# switches_connectors.net
KiCad netlist of a schematic drawn in Altium Designer
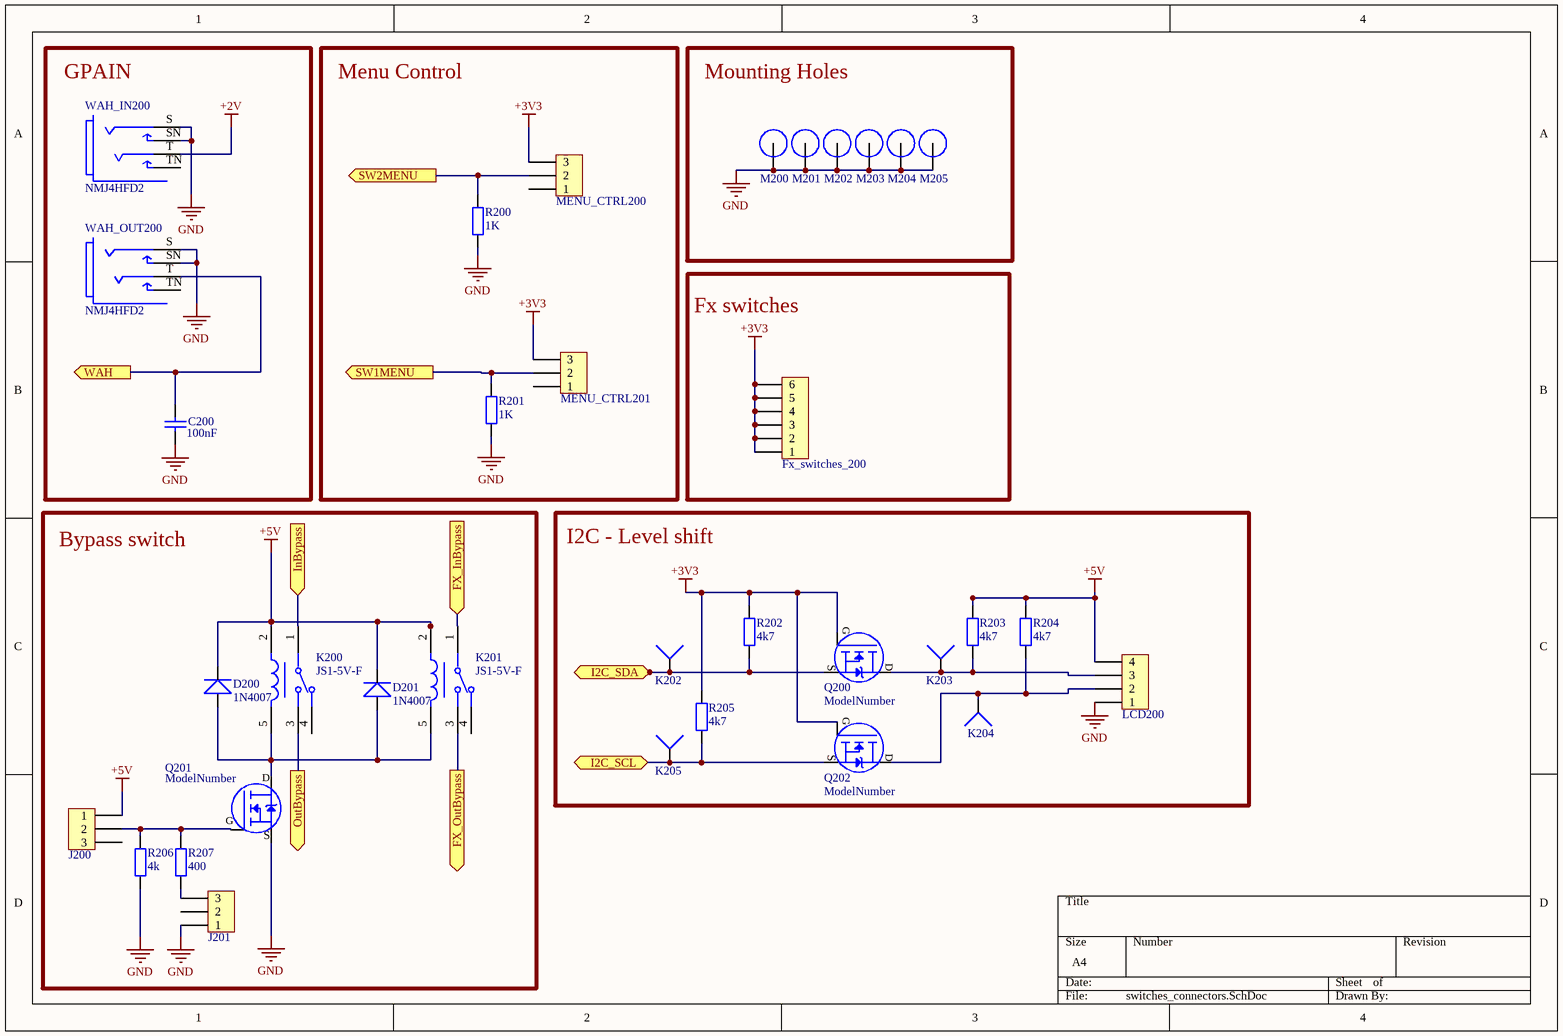
[diagram p0: switches_connectors.SchDoc]

(export (version "E")
  (design (tool "Eeschema 10.0.6"))
  (components
    (comp (ref "C200")
      (value "100nF")
      (footprint "Cap-1")
      (fields (field (name "Comment") "Cap"))
      (libsource (lib "AAURacing") (part "Capacitor 1 space"))
    )
    (comp (ref "D200")
      (value "1N4007")
      (footprint "1N4007")
      (libsource (lib "mit_seje_library") (part "1N4007"))
    )
    (comp (ref "D201")
      (value "1N4007")
      (footprint "1N4007")
      (libsource (lib "mit_seje_library") (part "1N4007"))
    )
    (comp (ref "Fx_switches_200")
      (value "Header 1x6")
      (footprint "Header 1x6")
      (libsource (lib "AAURacing") (part "Header 1x6"))
    )
    (comp (ref "J200")
      (value "Header 1x3")
      (footprint "Header 1x3")
      (libsource (lib "") (part "Header 1x3_1"))
    )
    (comp (ref "J201")
      (value "Header 1x3")
      (footprint "Header 1x3")
      (libsource (lib "AAURacing") (part "Header 1x3"))
    )
    (comp (ref "K200")
      (value "JS1-5V-F")
      (footprint "FP-JS1-5V-F-MFG")
      (description "RELAY GEN PURPOSE SPDT 10A 5V")
      (fields
        (field (name "OCTOPART") "https://octopart.com/js1-5v-f-panasonic-39428621")
        (field (name "MANUFACTURER") "Panasonic")
      )
      (libsource (lib "Altium Content Vault") (part "250623531296f86beaf95f2bc4a6d4c"))
    )
    (comp (ref "K201")
      (value "JS1-5V-F")
      (footprint "FP-JS1-5V-F-MFG")
      (description "RELAY GEN PURPOSE SPDT 10A 5V")
      (fields
        (field (name "OCTOPART") "https://octopart.com/js1-5v-f-panasonic-39428621")
        (field (name "MANUFACTURER") "Panasonic")
      )
      (libsource (lib "Altium Content Vault") (part "250623531296f86beaf95f2bc4a6d4c"))
    )
    (comp (ref "K202") (value "Wire") (footprint "Wire 1.5mm") (libsource (lib "AAURacing") (part "Wire")))
    (comp (ref "K203") (value "Wire") (footprint "Wire 1.5mm") (libsource (lib "AAURacing") (part "Wire")))
    (comp (ref "K204") (value "Wire") (footprint "Wire 1.5mm") (libsource (lib "AAURacing") (part "Wire")))
    (comp (ref "K205") (value "Wire") (footprint "Wire 1.5mm") (libsource (lib "AAURacing") (part "Wire")))
    (comp (ref "LCD200")
      (value "Header 1x4")
      (footprint "Header 1x4")
      (libsource (lib "AAURacing") (part "Header 1x4"))
    )
    (comp (ref "M200")
      (value "Screw Hole")
      (footprint "M3 Hole")
      (libsource (lib "AAURacing") (part "Screw Hole"))
    )
    (comp (ref "M201")
      (value "Screw Hole")
      (footprint "M3 Hole")
      (libsource (lib "AAURacing") (part "Screw Hole"))
    )
    (comp (ref "M202")
      (value "Screw Hole")
      (footprint "M3 Hole")
      (libsource (lib "AAURacing") (part "Screw Hole"))
    )
    (comp (ref "M203")
      (value "Screw Hole")
      (footprint "M3 Hole")
      (libsource (lib "AAURacing") (part "Screw Hole"))
    )
    (comp (ref "M204")
      (value "Screw Hole")
      (footprint "M3 Hole")
      (libsource (lib "AAURacing") (part "Screw Hole"))
    )
    (comp (ref "M205")
      (value "Screw Hole")
      (footprint "M3 Hole")
      (libsource (lib "AAURacing") (part "Screw Hole"))
    )
    (comp (ref "MENU_CTRL200")
      (value "Header 1x3")
      (footprint "Header 1x3")
      (libsource (lib "AAURacing") (part "Header 1x3"))
    )
    (comp (ref "MENU_CTRL201")
      (value "Header 1x3")
      (footprint "Header 1x3")
      (libsource (lib "AAURacing") (part "Header 1x3"))
    )
    (comp (ref "Q200")
      (value "ModelNum")
      (footprint "TO-92_straight")
      (fields (field (name "MODEL") "ModelNumber"))
      (libsource (lib "AAURacing") (part "MOSFET N-Channel"))
    )
    (comp (ref "Q201")
      (value "ModelNum")
      (footprint "TO-220")
      (fields (field (name "MODEL") "ModelNumber"))
      (libsource (lib "AAURacing") (part "MOSFET N-Channel"))
    )
    (comp (ref "Q202")
      (value "ModelNum")
      (footprint "TO-92_straight")
      (fields (field (name "MODEL") "ModelNumber"))
      (libsource (lib "AAURacing") (part "MOSFET N-Channel"))
    )
    (comp (ref "R200")
      (value "1K")
      (footprint "RES THT 9mm")
      (fields (field (name "Comment") "Resistor"))
      (libsource (lib "AAURacing") (part "Resistor"))
    )
    (comp (ref "R201")
      (value "1K")
      (footprint "RES THT 9mm")
      (fields (field (name "Comment") "Resistor"))
      (libsource (lib "AAURacing") (part "Resistor"))
    )
    (comp (ref "R202")
      (value "4k7")
      (footprint "RES THT 9mm")
      (fields (field (name "Comment") "Resistor"))
      (libsource (lib "AAURacing") (part "Resistor"))
    )
    (comp (ref "R203")
      (value "4k7")
      (footprint "RES THT 9mm")
      (fields (field (name "Comment") "Resistor"))
      (libsource (lib "AAURacing") (part "Resistor"))
    )
    (comp (ref "R204")
      (value "4k7")
      (footprint "RES THT 9mm")
      (fields (field (name "Comment") "Resistor"))
      (libsource (lib "AAURacing") (part "Resistor"))
    )
    (comp (ref "R205")
      (value "4k7")
      (footprint "RES THT 9mm")
      (fields (field (name "Comment") "Resistor"))
      (libsource (lib "AAURacing") (part "Resistor"))
    )
    (comp (ref "R206")
      (value "4k")
      (footprint "RES THT 9mm")
      (fields (field (name "Comment") "Resistor"))
      (libsource (lib "AAURacing") (part "Resistor"))
    )
    (comp (ref "R207")
      (value "400")
      (footprint "RES THT 9mm")
      (fields (field (name "Comment") "Resistor"))
      (libsource (lib "AAURacing") (part "Resistor"))
    )
    (comp (ref "WAH_IN200")
      (value "NMJ4HFD2")
      (footprint "FP-NMJ4HFD2-MFG")
      (description "Conn 1/4\" Mono Jack F 3 POS Solder RA Thru-Hole 3 Terminal 1 Port")
      (fields
        (field (name "MANUFACTURER") "Neutrik")
        (field (name "OCTOPART") "https://octopart.com/nmj4hfd2-neutrik-758952")
      )
      (libsource (lib "Altium Content Vault") (part "8c9933f05338f077543a5425baeefa5"))
    )
    (comp (ref "WAH_OUT200")
      (value "NMJ4HFD2")
      (footprint "FP-NMJ4HFD2-MFG")
      (description "Conn 1/4\" Mono Jack F 3 POS Solder RA Thru-Hole 3 Terminal 1 Port")
      (fields
        (field (name "MANUFACTURER") "Neutrik")
        (field (name "OCTOPART") "https://octopart.com/nmj4hfd2-neutrik-758952")
      )
      (libsource (lib "Altium Content Vault") (part "8c9933f05338f077543a5425baeefa5"))
    )
  )
  (nets
    (net (code "1") (name "+2V") (class "Default")
      (node (ref "WAH_IN200") (pin "T") (pinfunction "T_T") (pintype "passive"))
    )
    (net (code "2") (name "+3V3") (class "Default")
      (node (ref "Fx_switches_200") (pin "1") (pinfunction "1_1") (pintype "passive"))
      (node (ref "Fx_switches_200") (pin "2") (pinfunction "2_2") (pintype "passive"))
      (node (ref "Fx_switches_200") (pin "3") (pinfunction "3_3") (pintype "passive"))
      (node (ref "Fx_switches_200") (pin "4") (pinfunction "4_4") (pintype "passive"))
      (node (ref "Fx_switches_200") (pin "5") (pinfunction "5_5") (pintype "passive"))
      (node (ref "Fx_switches_200") (pin "6") (pinfunction "6_6") (pintype "passive"))
      (node (ref "MENU_CTRL200") (pin "3") (pinfunction "3_3") (pintype "passive"))
      (node (ref "MENU_CTRL201") (pin "3") (pinfunction "3_3") (pintype "passive"))
      (node (ref "Q200") (pin "1") (pinfunction "G_1") (pintype "passive"))
      (node (ref "Q202") (pin "1") (pinfunction "G_1") (pintype "passive"))
      (node (ref "R202") (pin "2") (pinfunction "2_2") (pintype "passive"))
      (node (ref "R205") (pin "2") (pinfunction "2_2") (pintype "passive"))
    )
    (net (code "3") (name "+5V") (class "Default")
      (node (ref "D200") (pin "2") (pinfunction "2_2") (pintype "passive"))
      (node (ref "D201") (pin "2") (pinfunction "2_2") (pintype "passive"))
      (node (ref "J200") (pin "1") (pinfunction "1_1") (pintype "passive"))
      (node (ref "K200") (pin "2") (pinfunction "1_COIL_2") (pintype "passive"))
      (node (ref "K201") (pin "2") (pinfunction "1_COIL_2") (pintype "passive"))
      (node (ref "LCD200") (pin "4") (pinfunction "4_4") (pintype "passive"))
      (node (ref "R203") (pin "2") (pinfunction "2_2") (pintype "passive"))
      (node (ref "R204") (pin "2") (pinfunction "2_2") (pintype "passive"))
    )
    (net (code "4") (name "/FX_InBypass") (class "Default")
      (node (ref "K201") (pin "1") (pinfunction "COM_1") (pintype "passive"))
    )
    (net (code "5") (name "/FX_OutBypass") (class "Default")
      (node (ref "K201") (pin "3") (pinfunction "N.O._3") (pintype "passive"))
    )
    (net (code "6") (name "/I2C_SCL") (class "Default")
      (node (ref "K205") (pin "1") (pinfunction "1_1") (pintype "passive"))
      (node (ref "Q202") (pin "3") (pinfunction "S_3") (pintype "passive"))
      (node (ref "R205") (pin "1") (pinfunction "1_1") (pintype "passive"))
    )
    (net (code "7") (name "/I2C_SDA") (class "Default")
      (node (ref "K202") (pin "1") (pinfunction "1_1") (pintype "passive"))
      (node (ref "Q200") (pin "3") (pinfunction "S_3") (pintype "passive"))
      (node (ref "R202") (pin "1") (pinfunction "1_1") (pintype "passive"))
    )
    (net (code "8") (name "/InBypass") (class "Default")
      (node (ref "K200") (pin "1") (pinfunction "COM_1") (pintype "passive"))
    )
    (net (code "9") (name "/OutBypass") (class "Default")
      (node (ref "K200") (pin "3") (pinfunction "N.O._3") (pintype "passive"))
    )
    (net (code "10") (name "/SW1MENU") (class "Default")
      (node (ref "MENU_CTRL201") (pin "2") (pinfunction "2_2") (pintype "passive"))
      (node (ref "R201") (pin "2") (pinfunction "2_2") (pintype "passive"))
    )
    (net (code "11") (name "/SW2MENU") (class "Default")
      (node (ref "MENU_CTRL200") (pin "2") (pinfunction "2_2") (pintype "passive"))
      (node (ref "R200") (pin "2") (pinfunction "2_2") (pintype "passive"))
    )
    (net (code "12") (name "/WAH") (class "Default")
      (node (ref "C200") (pin "2") (pinfunction "g_2") (pintype "passive"))
      (node (ref "WAH_OUT200") (pin "T") (pinfunction "T_T") (pintype "passive"))
    )
    (net (code "13") (name "GND") (class "Default")
      (node (ref "C200") (pin "1") (pinfunction "1_1") (pintype "passive"))
      (node (ref "J201") (pin "1") (pinfunction "1_1") (pintype "passive"))
      (node (ref "LCD200") (pin "1") (pinfunction "1_1") (pintype "passive"))
      (node (ref "M200") (pin "1") (pinfunction "1_1") (pintype "passive"))
      (node (ref "M201") (pin "1") (pinfunction "1_1") (pintype "passive"))
      (node (ref "M202") (pin "1") (pinfunction "1_1") (pintype "passive"))
      (node (ref "M203") (pin "1") (pinfunction "1_1") (pintype "passive"))
      (node (ref "M204") (pin "1") (pinfunction "1_1") (pintype "passive"))
      (node (ref "M205") (pin "1") (pinfunction "1_1") (pintype "passive"))
      (node (ref "Q201") (pin "3") (pinfunction "S_3") (pintype "passive"))
      (node (ref "R200") (pin "1") (pinfunction "1_1") (pintype "passive"))
      (node (ref "R201") (pin "1") (pinfunction "1_1") (pintype "passive"))
      (node (ref "R206") (pin "1") (pinfunction "1_1") (pintype "passive"))
      (node (ref "WAH_IN200") (pin "S") (pinfunction "S_S") (pintype "passive"))
      (node (ref "WAH_IN200") (pin "SN") (pinfunction "SN_SN") (pintype "passive"))
      (node (ref "WAH_OUT200") (pin "S") (pinfunction "S_S") (pintype "passive"))
      (node (ref "WAH_OUT200") (pin "SN") (pinfunction "SN_SN") (pintype "passive"))
    )
    (net (code "14") (name "Net-(J201-Pad3)") (class "Default")
      (node (ref "J201") (pin "3") (pinfunction "3_3") (pintype "passive"))
      (node (ref "R207") (pin "1") (pinfunction "1_1") (pintype "passive"))
    )
    (net (code "15") (name "Net-(K200-2_COIL)") (class "Default")
      (node (ref "D200") (pin "1") (pinfunction "1_1") (pintype "passive"))
      (node (ref "D201") (pin "1") (pinfunction "1_1") (pintype "passive"))
      (node (ref "K200") (pin "5") (pinfunction "2_COIL_5") (pintype "passive"))
      (node (ref "K201") (pin "5") (pinfunction "2_COIL_5") (pintype "passive"))
      (node (ref "Q201") (pin "2") (pinfunction "D_2") (pintype "passive"))
    )
    (net (code "16") (name "Net-(Q200-D)") (class "Default")
      (node (ref "K203") (pin "1") (pinfunction "1_1") (pintype "passive"))
      (node (ref "LCD200") (pin "3") (pinfunction "3_3") (pintype "passive"))
      (node (ref "Q200") (pin "2") (pinfunction "D_2") (pintype "passive"))
      (node (ref "R203") (pin "1") (pinfunction "1_1") (pintype "passive"))
    )
    (net (code "17") (name "Net-(Q201-G)") (class "Default")
      (node (ref "J200") (pin "2") (pinfunction "2_2") (pintype "passive"))
      (node (ref "Q201") (pin "1") (pinfunction "G_1") (pintype "passive"))
      (node (ref "R206") (pin "2") (pinfunction "2_2") (pintype "passive"))
      (node (ref "R207") (pin "2") (pinfunction "2_2") (pintype "passive"))
    )
    (net (code "18") (name "Net-(Q202-D)") (class "Default")
      (node (ref "K204") (pin "1") (pinfunction "1_1") (pintype "passive"))
      (node (ref "LCD200") (pin "2") (pinfunction "2_2") (pintype "passive"))
      (node (ref "Q202") (pin "2") (pinfunction "D_2") (pintype "passive"))
      (node (ref "R204") (pin "1") (pinfunction "1_1") (pintype "passive"))
    )
    (net (code "19") (name "unconnected-(J200-Pad3)") (class "Default")
      (node (ref "J200") (pin "3") (pinfunction "3_3") (pintype "passive"))
    )
    (net (code "20") (name "unconnected-(J201-Pad2)") (class "Default")
      (node (ref "J201") (pin "2") (pinfunction "2_2") (pintype "passive"))
    )
    (net (code "21") (name "unconnected-(K200-N.C.-Pad4)") (class "Default")
      (node (ref "K200") (pin "4") (pinfunction "N.C._4") (pintype "passive"))
    )
    (net (code "22") (name "unconnected-(K201-N.C.-Pad4)") (class "Default")
      (node (ref "K201") (pin "4") (pinfunction "N.C._4") (pintype "passive"))
    )
    (net (code "23") (name "unconnected-(MENU_CTRL200-Pad1)") (class "Default")
      (node (ref "MENU_CTRL200") (pin "1") (pinfunction "1_1") (pintype "passive"))
    )
    (net (code "24") (name "unconnected-(MENU_CTRL201-Pad1)") (class "Default")
      (node (ref "MENU_CTRL201") (pin "1") (pinfunction "1_1") (pintype "passive"))
    )
    (net (code "25") (name "unconnected-(WAH_IN200-PadTN)") (class "Default")
      (node (ref "WAH_IN200") (pin "TN") (pinfunction "TN_TN") (pintype "passive"))
    )
    (net (code "26") (name "unconnected-(WAH_OUT200-PadTN)") (class "Default")
      (node (ref "WAH_OUT200") (pin "TN") (pinfunction "TN_TN") (pintype "passive"))
    )
  )
)
